# Trefferzonenmodul.net
KiCad netlist of a schematic drawn in EAGLE
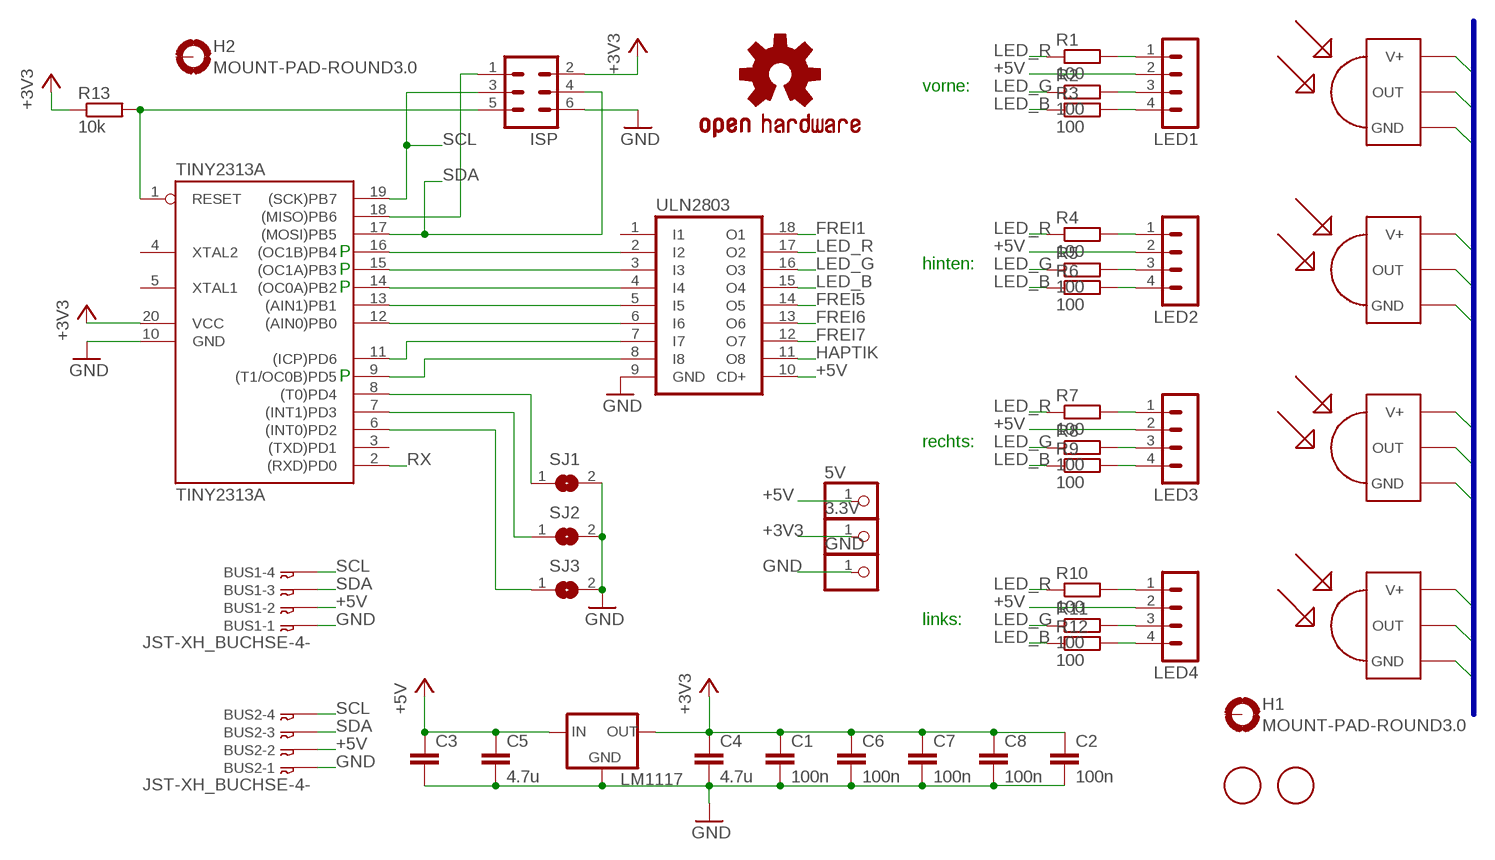
[diagram p0: schematic, sheet 1]

(export (version "E")
  (design (tool "Eeschema 10.0.6"))
  (components
    (comp (ref "3.3V")
      (value "PIN-HEADER-1")
      (footprint "eagle-import:PIN-HEADER-1")
      (libsource (lib "eagle-import") (part "PIN-HEADER-1"))
    )
    (comp (ref "5V")
      (value "PIN-HEADER-1")
      (footprint "eagle-import:PIN-HEADER-1")
      (libsource (lib "eagle-import") (part "PIN-HEADER-1"))
    )
    (comp (ref "BUS1")
      (value "JST-XH_BUCHSE-4-")
      (footprint "eagle-import:JST-XH_BUCHSE-4")
      (libsource (lib "eagle-import") (part "JST-XH_BUCHSE-4-"))
    )
    (comp (ref "BUS2")
      (value "JST-XH_BUCHSE-4-")
      (footprint "eagle-import:JST-XH_BUCHSE-4")
      (libsource (lib "eagle-import") (part "JST-XH_BUCHSE-4-"))
    )
    (comp (ref "C1")
      (value "100n")
      (footprint "eagle-import:0603")
      (libsource (lib "eagle-import") (part "C_EU0603"))
    )
    (comp (ref "C2")
      (value "100n")
      (footprint "eagle-import:0603")
      (libsource (lib "eagle-import") (part "C_EU0603"))
    )
    (comp (ref "C3")
      (value "C_EUCAP_UNIVERSAL")
      (footprint "eagle-import:C_UNIVERSAL")
      (libsource (lib "eagle-import") (part "C_EUCAP_UNIVERSAL"))
    )
    (comp (ref "C4")
      (value "4.7u")
      (footprint "eagle-import:0805")
      (libsource (lib "eagle-import") (part "C_EU0805"))
    )
    (comp (ref "C5")
      (value "4.7u")
      (footprint "eagle-import:0805")
      (libsource (lib "eagle-import") (part "C_EU0805"))
    )
    (comp (ref "C6")
      (value "100n")
      (footprint "eagle-import:0603")
      (libsource (lib "eagle-import") (part "C_EU0603"))
    )
    (comp (ref "C7")
      (value "100n")
      (footprint "eagle-import:0603")
      (libsource (lib "eagle-import") (part "C_EU0603"))
    )
    (comp (ref "C8")
      (value "100n")
      (footprint "eagle-import:0603")
      (libsource (lib "eagle-import") (part "C_EU0603"))
    )
    (comp (ref "GND")
      (value "PIN-HEADER-1")
      (footprint "eagle-import:PIN-HEADER-1")
      (libsource (lib "eagle-import") (part "PIN-HEADER-1"))
    )
    (comp (ref "H1")
      (value "MOUNT-PAD-ROUND3.0")
      (footprint "eagle-import:3,0-PAD")
      (libsource (lib "eagle-import") (part "MOUNT-PAD-ROUND3.0"))
    )
    (comp (ref "H2")
      (value "MOUNT-PAD-ROUND3.0")
      (footprint "eagle-import:3,0-PAD")
      (libsource (lib "eagle-import") (part "MOUNT-PAD-ROUND3.0"))
    )
    (comp (ref "ISP")
      (value "PIN-HEADER-3X2")
      (footprint "eagle-import:PIN-HEADER-3X2")
      (libsource (lib "eagle-import") (part "PIN-HEADER-3X2"))
    )
    (comp (ref "LED1")
      (value "PIN-HEADER-4")
      (footprint "eagle-import:PIN-HEADER-4")
      (libsource (lib "eagle-import") (part "PIN-HEADER-4"))
    )
    (comp (ref "LED2")
      (value "PIN-HEADER-4")
      (footprint "eagle-import:PIN-HEADER-4")
      (libsource (lib "eagle-import") (part "PIN-HEADER-4"))
    )
    (comp (ref "LED3")
      (value "PIN-HEADER-4")
      (footprint "eagle-import:PIN-HEADER-4")
      (libsource (lib "eagle-import") (part "PIN-HEADER-4"))
    )
    (comp (ref "LED4")
      (value "PIN-HEADER-4")
      (footprint "eagle-import:PIN-HEADER-4")
      (libsource (lib "eagle-import") (part "PIN-HEADER-4"))
    )
    (comp (ref "LM1117")
      (value "LM1117_3V3_REGULATOR")
      (footprint "eagle-import:SOT223")
      (libsource (lib "eagle-import") (part "LM1117_3V3_REGULATOR"))
    )
    (comp (ref "LOGO1")
      (value "OSHW-LOGOM")
      (footprint "eagle-import:OSHW-LOGO-M")
      (libsource (lib "eagle-import") (part "OSHW-LOGOM"))
    )
    (comp (ref "LOGO2")
      (value "OSHW-LOGOM")
      (footprint "eagle-import:OSHW-LOGO-M")
      (libsource (lib "eagle-import") (part "OSHW-LOGOM"))
    )
    (comp (ref "R1")
      (value "100")
      (footprint "eagle-import:0603")
      (libsource (lib "eagle-import") (part "R_EU0603"))
    )
    (comp (ref "R2")
      (value "100")
      (footprint "eagle-import:0603")
      (libsource (lib "eagle-import") (part "R_EU0603"))
    )
    (comp (ref "R3")
      (value "100")
      (footprint "eagle-import:0603")
      (libsource (lib "eagle-import") (part "R_EU0603"))
    )
    (comp (ref "R4")
      (value "100")
      (footprint "eagle-import:0603")
      (libsource (lib "eagle-import") (part "R_EU0603"))
    )
    (comp (ref "R5")
      (value "100")
      (footprint "eagle-import:0603")
      (libsource (lib "eagle-import") (part "R_EU0603"))
    )
    (comp (ref "R6")
      (value "100")
      (footprint "eagle-import:0603")
      (libsource (lib "eagle-import") (part "R_EU0603"))
    )
    (comp (ref "R7")
      (value "100")
      (footprint "eagle-import:0603")
      (libsource (lib "eagle-import") (part "R_EU0603"))
    )
    (comp (ref "R8")
      (value "100")
      (footprint "eagle-import:0603")
      (libsource (lib "eagle-import") (part "R_EU0603"))
    )
    (comp (ref "R9")
      (value "100")
      (footprint "eagle-import:0603")
      (libsource (lib "eagle-import") (part "R_EU0603"))
    )
    (comp (ref "R10")
      (value "100")
      (footprint "eagle-import:0603")
      (libsource (lib "eagle-import") (part "R_EU0603"))
    )
    (comp (ref "R11")
      (value "100")
      (footprint "eagle-import:0603")
      (libsource (lib "eagle-import") (part "R_EU0603"))
    )
    (comp (ref "R12")
      (value "100")
      (footprint "eagle-import:0603")
      (libsource (lib "eagle-import") (part "R_EU0603"))
    )
    (comp (ref "R13")
      (value "10k")
      (footprint "eagle-import:0603")
      (libsource (lib "eagle-import") (part "R_EU0603"))
    )
    (comp (ref "SJ1") (value "SJ") (footprint "eagle-import:SJ") (libsource (lib "eagle-import") (part "SJ")))
    (comp (ref "SJ2") (value "SJ") (footprint "eagle-import:SJ") (libsource (lib "eagle-import") (part "SJ")))
    (comp (ref "SJ3") (value "SJ") (footprint "eagle-import:SJ") (libsource (lib "eagle-import") (part "SJ")))
    (comp (ref "TINY2313A")
      (value "TINY2313A")
      (footprint "eagle-import:SO20LVERSTUMMELT")
      (libsource (lib "eagle-import") (part "TINY2313A"))
    )
    (comp (ref "U$1")
      (value "TSOP4338")
      (footprint "eagle-import:TSOP4338")
      (libsource (lib "eagle-import") (part "TSOP4338"))
    )
    (comp (ref "U$2")
      (value "TSOP4338")
      (footprint "eagle-import:TSOP4338")
      (libsource (lib "eagle-import") (part "TSOP4338"))
    )
    (comp (ref "U$3")
      (value "TSOP4338")
      (footprint "eagle-import:TSOP4338")
      (libsource (lib "eagle-import") (part "TSOP4338"))
    )
    (comp (ref "U$4")
      (value "TSOP4338")
      (footprint "eagle-import:TSOP4338")
      (libsource (lib "eagle-import") (part "TSOP4338"))
    )
    (comp (ref "U$5")
      (value "FIDUCIAL")
      (footprint "eagle-import:FIDUCIAL_1MM")
      (libsource (lib "eagle-import") (part "FIDUCIAL"))
    )
    (comp (ref "U$6")
      (value "FIDUCIAL")
      (footprint "eagle-import:FIDUCIAL_1MM")
      (libsource (lib "eagle-import") (part "FIDUCIAL"))
    )
    (comp (ref "ULN2803")
      (value "ULN2803ASO18")
      (footprint "eagle-import:SO18W")
      (libsource (lib "eagle-import") (part "ULN2803ASO18"))
    )
  )
  (nets
    (net (code "1") (name "+3V3") (class "Default")
      (node (ref "3.3V") (pin "1") (pinfunction "1_1") (pintype "passive"))
      (node (ref "C1") (pin "1") (pinfunction "1_1") (pintype "passive"))
      (node (ref "C2") (pin "1") (pinfunction "1_1") (pintype "passive"))
      (node (ref "C4") (pin "1") (pinfunction "1_1") (pintype "passive"))
      (node (ref "C6") (pin "1") (pinfunction "1_1") (pintype "passive"))
      (node (ref "C7") (pin "1") (pinfunction "1_1") (pintype "passive"))
      (node (ref "C8") (pin "1") (pinfunction "1_1") (pintype "passive"))
      (node (ref "ISP") (pin "2") (pinfunction "2_2") (pintype "passive"))
      (node (ref "LM1117") (pin "2") (pinfunction "OUT_2") (pintype "passive"))
      (node (ref "LM1117") (pin "4") (pinfunction "OUT_4") (pintype "passive"))
      (node (ref "R13") (pin "1") (pinfunction "1_1") (pintype "passive"))
      (node (ref "TINY2313A") (pin "20") (pinfunction "VCC_20") (pintype "power_in"))
      (node (ref "U$1") (pin "VCC") (pinfunction "V+_VCC") (pintype "bidirectional"))
      (node (ref "U$2") (pin "VCC") (pinfunction "V+_VCC") (pintype "bidirectional"))
      (node (ref "U$3") (pin "VCC") (pinfunction "V+_VCC") (pintype "bidirectional"))
      (node (ref "U$4") (pin "VCC") (pinfunction "V+_VCC") (pintype "bidirectional"))
    )
    (net (code "2") (name "+5V") (class "Default")
      (node (ref "5V") (pin "1") (pinfunction "1_1") (pintype "passive"))
      (node (ref "BUS1") (pin "P$2") (pinfunction "1_P$2") (pintype "passive"))
      (node (ref "BUS2") (pin "P$2") (pinfunction "1_P$2") (pintype "passive"))
      (node (ref "C3") (pin "1") (pinfunction "1_1") (pintype "passive"))
      (node (ref "C3") (pin "1B") (pinfunction "1_1B") (pintype "passive"))
      (node (ref "C5") (pin "1") (pinfunction "1_1") (pintype "passive"))
      (node (ref "LED1") (pin "2") (pinfunction "2_2") (pintype "passive"))
      (node (ref "LED2") (pin "2") (pinfunction "2_2") (pintype "passive"))
      (node (ref "LED3") (pin "2") (pinfunction "2_2") (pintype "passive"))
      (node (ref "LED4") (pin "2") (pinfunction "2_2") (pintype "passive"))
      (node (ref "LM1117") (pin "3") (pinfunction "IN_3") (pintype "input"))
      (node (ref "ULN2803") (pin "10") (pinfunction "CD+_10") (pintype "passive"))
    )
    (net (code "3") (name "/FREI1") (class "Default")
      (node (ref "ULN2803") (pin "18") (pinfunction "O1_18") (pintype "open_collector"))
    )
    (net (code "4") (name "/FREI5") (class "Default")
      (node (ref "ULN2803") (pin "14") (pinfunction "O5_14") (pintype "open_collector"))
    )
    (net (code "5") (name "/FREI6") (class "Default")
      (node (ref "ULN2803") (pin "13") (pinfunction "O6_13") (pintype "open_collector"))
    )
    (net (code "6") (name "/FREI7") (class "Default")
      (node (ref "ULN2803") (pin "12") (pinfunction "O7_12") (pintype "open_collector"))
    )
    (net (code "7") (name "/HAPTIK") (class "Default")
      (node (ref "ULN2803") (pin "11") (pinfunction "O8_11") (pintype "open_collector"))
    )
    (net (code "8") (name "/LED_B") (class "Default")
      (node (ref "R12") (pin "1") (pinfunction "1_1") (pintype "passive"))
      (node (ref "R3") (pin "1") (pinfunction "1_1") (pintype "passive"))
      (node (ref "R6") (pin "1") (pinfunction "1_1") (pintype "passive"))
      (node (ref "R9") (pin "1") (pinfunction "1_1") (pintype "passive"))
      (node (ref "ULN2803") (pin "15") (pinfunction "O4_15") (pintype "open_collector"))
    )
    (net (code "9") (name "/LED_G") (class "Default")
      (node (ref "R11") (pin "1") (pinfunction "1_1") (pintype "passive"))
      (node (ref "R2") (pin "1") (pinfunction "1_1") (pintype "passive"))
      (node (ref "R5") (pin "1") (pinfunction "1_1") (pintype "passive"))
      (node (ref "R8") (pin "1") (pinfunction "1_1") (pintype "passive"))
      (node (ref "ULN2803") (pin "16") (pinfunction "O3_16") (pintype "open_collector"))
    )
    (net (code "10") (name "/LED_R") (class "Default")
      (node (ref "R1") (pin "1") (pinfunction "1_1") (pintype "passive"))
      (node (ref "R10") (pin "1") (pinfunction "1_1") (pintype "passive"))
      (node (ref "R4") (pin "1") (pinfunction "1_1") (pintype "passive"))
      (node (ref "R7") (pin "1") (pinfunction "1_1") (pintype "passive"))
      (node (ref "ULN2803") (pin "17") (pinfunction "O2_17") (pintype "open_collector"))
    )
    (net (code "11") (name "/RX") (class "Default")
      (node (ref "TINY2313A") (pin "2") (pinfunction "(RXD)PD0_2") (pintype "bidirectional"))
      (node (ref "U$1") (pin "OUT") (pinfunction "OUT_OUT") (pintype "bidirectional"))
      (node (ref "U$2") (pin "OUT") (pinfunction "OUT_OUT") (pintype "bidirectional"))
      (node (ref "U$3") (pin "OUT") (pinfunction "OUT_OUT") (pintype "bidirectional"))
      (node (ref "U$4") (pin "OUT") (pinfunction "OUT_OUT") (pintype "bidirectional"))
    )
    (net (code "12") (name "/SCL") (class "Default")
      (node (ref "BUS1") (pin "P$4") (pinfunction "1_P$4") (pintype "passive"))
      (node (ref "BUS2") (pin "P$4") (pinfunction "1_P$4") (pintype "passive"))
      (node (ref "ISP") (pin "3") (pinfunction "3_3") (pintype "passive"))
      (node (ref "TINY2313A") (pin "19") (pinfunction "(SCK)PB7_19") (pintype "bidirectional"))
    )
    (net (code "13") (name "/SDA") (class "Default")
      (node (ref "BUS1") (pin "P$3") (pinfunction "1_P$3") (pintype "passive"))
      (node (ref "BUS2") (pin "P$3") (pinfunction "1_P$3") (pintype "passive"))
      (node (ref "ISP") (pin "4") (pinfunction "4_4") (pintype "passive"))
      (node (ref "TINY2313A") (pin "17") (pinfunction "(MOSI)PB5_17") (pintype "bidirectional"))
    )
    (net (code "14") (name "GND") (class "Default")
      (node (ref "BUS1") (pin "P$1") (pinfunction "1_P$1") (pintype "passive"))
      (node (ref "BUS2") (pin "P$1") (pinfunction "1_P$1") (pintype "passive"))
      (node (ref "C1") (pin "2") (pinfunction "2_2") (pintype "passive"))
      (node (ref "C2") (pin "2") (pinfunction "2_2") (pintype "passive"))
      (node (ref "C3") (pin "2") (pinfunction "2_2") (pintype "passive"))
      (node (ref "C3") (pin "2B") (pinfunction "2_2B") (pintype "passive"))
      (node (ref "C4") (pin "2") (pinfunction "2_2") (pintype "passive"))
      (node (ref "C5") (pin "2") (pinfunction "2_2") (pintype "passive"))
      (node (ref "C6") (pin "2") (pinfunction "2_2") (pintype "passive"))
      (node (ref "C7") (pin "2") (pinfunction "2_2") (pintype "passive"))
      (node (ref "C8") (pin "2") (pinfunction "2_2") (pintype "passive"))
      (node (ref "GND") (pin "1") (pinfunction "1_1") (pintype "passive"))
      (node (ref "ISP") (pin "6") (pinfunction "6_6") (pintype "passive"))
      (node (ref "LM1117") (pin "1") (pinfunction "GND_1") (pintype "input"))
      (node (ref "SJ1") (pin "2") (pinfunction "2_2") (pintype "passive"))
      (node (ref "SJ2") (pin "2") (pinfunction "2_2") (pintype "passive"))
      (node (ref "SJ3") (pin "2") (pinfunction "2_2") (pintype "passive"))
      (node (ref "TINY2313A") (pin "10") (pinfunction "GND_10") (pintype "power_in"))
      (node (ref "U$1") (pin "GND") (pinfunction "GND_GND") (pintype "bidirectional"))
      (node (ref "U$2") (pin "GND") (pinfunction "GND_GND") (pintype "bidirectional"))
      (node (ref "U$3") (pin "GND") (pinfunction "GND_GND") (pintype "bidirectional"))
      (node (ref "U$4") (pin "GND") (pinfunction "GND_GND") (pintype "bidirectional"))
      (node (ref "ULN2803") (pin "9") (pinfunction "GND_9") (pintype "power_in"))
    )
    (net (code "15") (name "Net-(LED1-Pad1)") (class "Default")
      (node (ref "LED1") (pin "1") (pinfunction "1_1") (pintype "passive"))
      (node (ref "R1") (pin "2") (pinfunction "2_2") (pintype "passive"))
    )
    (net (code "16") (name "Net-(LED1-Pad3)") (class "Default")
      (node (ref "LED1") (pin "3") (pinfunction "3_3") (pintype "passive"))
      (node (ref "R2") (pin "2") (pinfunction "2_2") (pintype "passive"))
    )
    (net (code "17") (name "Net-(LED1-Pad4)") (class "Default")
      (node (ref "LED1") (pin "4") (pinfunction "4_4") (pintype "passive"))
      (node (ref "R3") (pin "2") (pinfunction "2_2") (pintype "passive"))
    )
    (net (code "18") (name "Net-(LED2-Pad1)") (class "Default")
      (node (ref "LED2") (pin "1") (pinfunction "1_1") (pintype "passive"))
      (node (ref "R4") (pin "2") (pinfunction "2_2") (pintype "passive"))
    )
    (net (code "19") (name "Net-(LED2-Pad3)") (class "Default")
      (node (ref "LED2") (pin "3") (pinfunction "3_3") (pintype "passive"))
      (node (ref "R5") (pin "2") (pinfunction "2_2") (pintype "passive"))
    )
    (net (code "20") (name "Net-(LED2-Pad4)") (class "Default")
      (node (ref "LED2") (pin "4") (pinfunction "4_4") (pintype "passive"))
      (node (ref "R6") (pin "2") (pinfunction "2_2") (pintype "passive"))
    )
    (net (code "21") (name "Net-(LED3-Pad1)") (class "Default")
      (node (ref "LED3") (pin "1") (pinfunction "1_1") (pintype "passive"))
      (node (ref "R7") (pin "2") (pinfunction "2_2") (pintype "passive"))
    )
    (net (code "22") (name "Net-(LED3-Pad3)") (class "Default")
      (node (ref "LED3") (pin "3") (pinfunction "3_3") (pintype "passive"))
      (node (ref "R8") (pin "2") (pinfunction "2_2") (pintype "passive"))
    )
    (net (code "23") (name "Net-(LED3-Pad4)") (class "Default")
      (node (ref "LED3") (pin "4") (pinfunction "4_4") (pintype "passive"))
      (node (ref "R9") (pin "2") (pinfunction "2_2") (pintype "passive"))
    )
    (net (code "24") (name "Net-(LED4-Pad1)") (class "Default")
      (node (ref "LED4") (pin "1") (pinfunction "1_1") (pintype "passive"))
      (node (ref "R10") (pin "2") (pinfunction "2_2") (pintype "passive"))
    )
    (net (code "25") (name "Net-(LED4-Pad3)") (class "Default")
      (node (ref "LED4") (pin "3") (pinfunction "3_3") (pintype "passive"))
      (node (ref "R11") (pin "2") (pinfunction "2_2") (pintype "passive"))
    )
    (net (code "26") (name "Net-(LED4-Pad4)") (class "Default")
      (node (ref "LED4") (pin "4") (pinfunction "4_4") (pintype "passive"))
      (node (ref "R12") (pin "2") (pinfunction "2_2") (pintype "passive"))
    )
    (net (code "27") (name "Net-(TINY2313A-(AIN0)PB0)") (class "Default")
      (node (ref "TINY2313A") (pin "12") (pinfunction "(AIN0)PB0_12") (pintype "bidirectional"))
      (node (ref "ULN2803") (pin "6") (pinfunction "I6_6") (pintype "input"))
    )
    (net (code "28") (name "Net-(TINY2313A-(AIN1)PB1)") (class "Default")
      (node (ref "TINY2313A") (pin "13") (pinfunction "(AIN1)PB1_13") (pintype "bidirectional"))
      (node (ref "ULN2803") (pin "5") (pinfunction "I5_5") (pintype "input"))
    )
    (net (code "29") (name "Net-(TINY2313A-(ICP)PD6)") (class "Default")
      (node (ref "TINY2313A") (pin "11") (pinfunction "(ICP)PD6_11") (pintype "bidirectional"))
      (node (ref "ULN2803") (pin "7") (pinfunction "I7_7") (pintype "input"))
    )
    (net (code "30") (name "Net-(TINY2313A-(INT0)PD2)") (class "Default")
      (node (ref "SJ3") (pin "1") (pinfunction "1_1") (pintype "passive"))
      (node (ref "TINY2313A") (pin "6") (pinfunction "(INT0)PD2_6") (pintype "bidirectional"))
    )
    (net (code "31") (name "Net-(TINY2313A-(INT1)PD3)") (class "Default")
      (node (ref "SJ2") (pin "1") (pinfunction "1_1") (pintype "passive"))
      (node (ref "TINY2313A") (pin "7") (pinfunction "(INT1)PD3_7") (pintype "bidirectional"))
    )
    (net (code "32") (name "Net-(TINY2313A-(MISO)PB6)") (class "Default")
      (node (ref "ISP") (pin "1") (pinfunction "1_1") (pintype "passive"))
      (node (ref "TINY2313A") (pin "18") (pinfunction "(MISO)PB6_18") (pintype "bidirectional"))
    )
    (net (code "33") (name "Net-(TINY2313A-(OC0A)PB2)") (class "Default")
      (node (ref "TINY2313A") (pin "14") (pinfunction "(OC0A)PB2_14") (pintype "bidirectional"))
      (node (ref "ULN2803") (pin "4") (pinfunction "I4_4") (pintype "input"))
    )
    (net (code "34") (name "Net-(TINY2313A-(OC1A)PB3)") (class "Default")
      (node (ref "TINY2313A") (pin "15") (pinfunction "(OC1A)PB3_15") (pintype "bidirectional"))
      (node (ref "ULN2803") (pin "3") (pinfunction "I3_3") (pintype "input"))
    )
    (net (code "35") (name "Net-(TINY2313A-(OC1B)PB4)") (class "Default")
      (node (ref "TINY2313A") (pin "16") (pinfunction "(OC1B)PB4_16") (pintype "bidirectional"))
      (node (ref "ULN2803") (pin "2") (pinfunction "I2_2") (pintype "input"))
    )
    (net (code "36") (name "Net-(TINY2313A-(T0)PD4)") (class "Default")
      (node (ref "SJ1") (pin "1") (pinfunction "1_1") (pintype "passive"))
      (node (ref "TINY2313A") (pin "8") (pinfunction "(T0)PD4_8") (pintype "bidirectional"))
    )
    (net (code "37") (name "Net-(TINY2313A-(T1{slash}OC0B)PD5)") (class "Default")
      (node (ref "TINY2313A") (pin "9") (pinfunction "(T1/OC0B)PD5_9") (pintype "bidirectional"))
      (node (ref "ULN2803") (pin "8") (pinfunction "I8_8") (pintype "input"))
    )
    (net (code "38") (name "Net-(TINY2313A-RESET)") (class "Default")
      (node (ref "ISP") (pin "5") (pinfunction "5_5") (pintype "passive"))
      (node (ref "R13") (pin "2") (pinfunction "2_2") (pintype "passive"))
      (node (ref "TINY2313A") (pin "1") (pinfunction "RESET_1") (pintype "bidirectional"))
    )
    (net (code "39") (name "unconnected-(H1-MOUNT-PadB3,0)") (class "Default")
      (node (ref "H1") (pin "B3,0") (pinfunction "MOUNT_B3,0") (pintype "passive"))
    )
    (net (code "40") (name "unconnected-(H2-MOUNT-PadB3,0)") (class "Default")
      (node (ref "H2") (pin "B3,0") (pinfunction "MOUNT_B3,0") (pintype "passive"))
    )
    (net (code "41") (name "unconnected-(TINY2313A-(TXD)PD1-Pad3)") (class "Default")
      (node (ref "TINY2313A") (pin "3") (pinfunction "(TXD)PD1_3") (pintype "bidirectional"))
    )
    (net (code "42") (name "unconnected-(TINY2313A-XTAL1-Pad5)") (class "Default")
      (node (ref "TINY2313A") (pin "5") (pinfunction "XTAL1_5") (pintype "bidirectional"))
    )
    (net (code "43") (name "unconnected-(TINY2313A-XTAL2-Pad4)") (class "Default")
      (node (ref "TINY2313A") (pin "4") (pinfunction "XTAL2_4") (pintype "bidirectional"))
    )
    (net (code "44") (name "unconnected-(ULN2803-I1-Pad1)") (class "Default")
      (node (ref "ULN2803") (pin "1") (pinfunction "I1_1") (pintype "input"))
    )
  )
)
